# MyPO.net
KiCad netlist of a schematic drawn in EAGLE
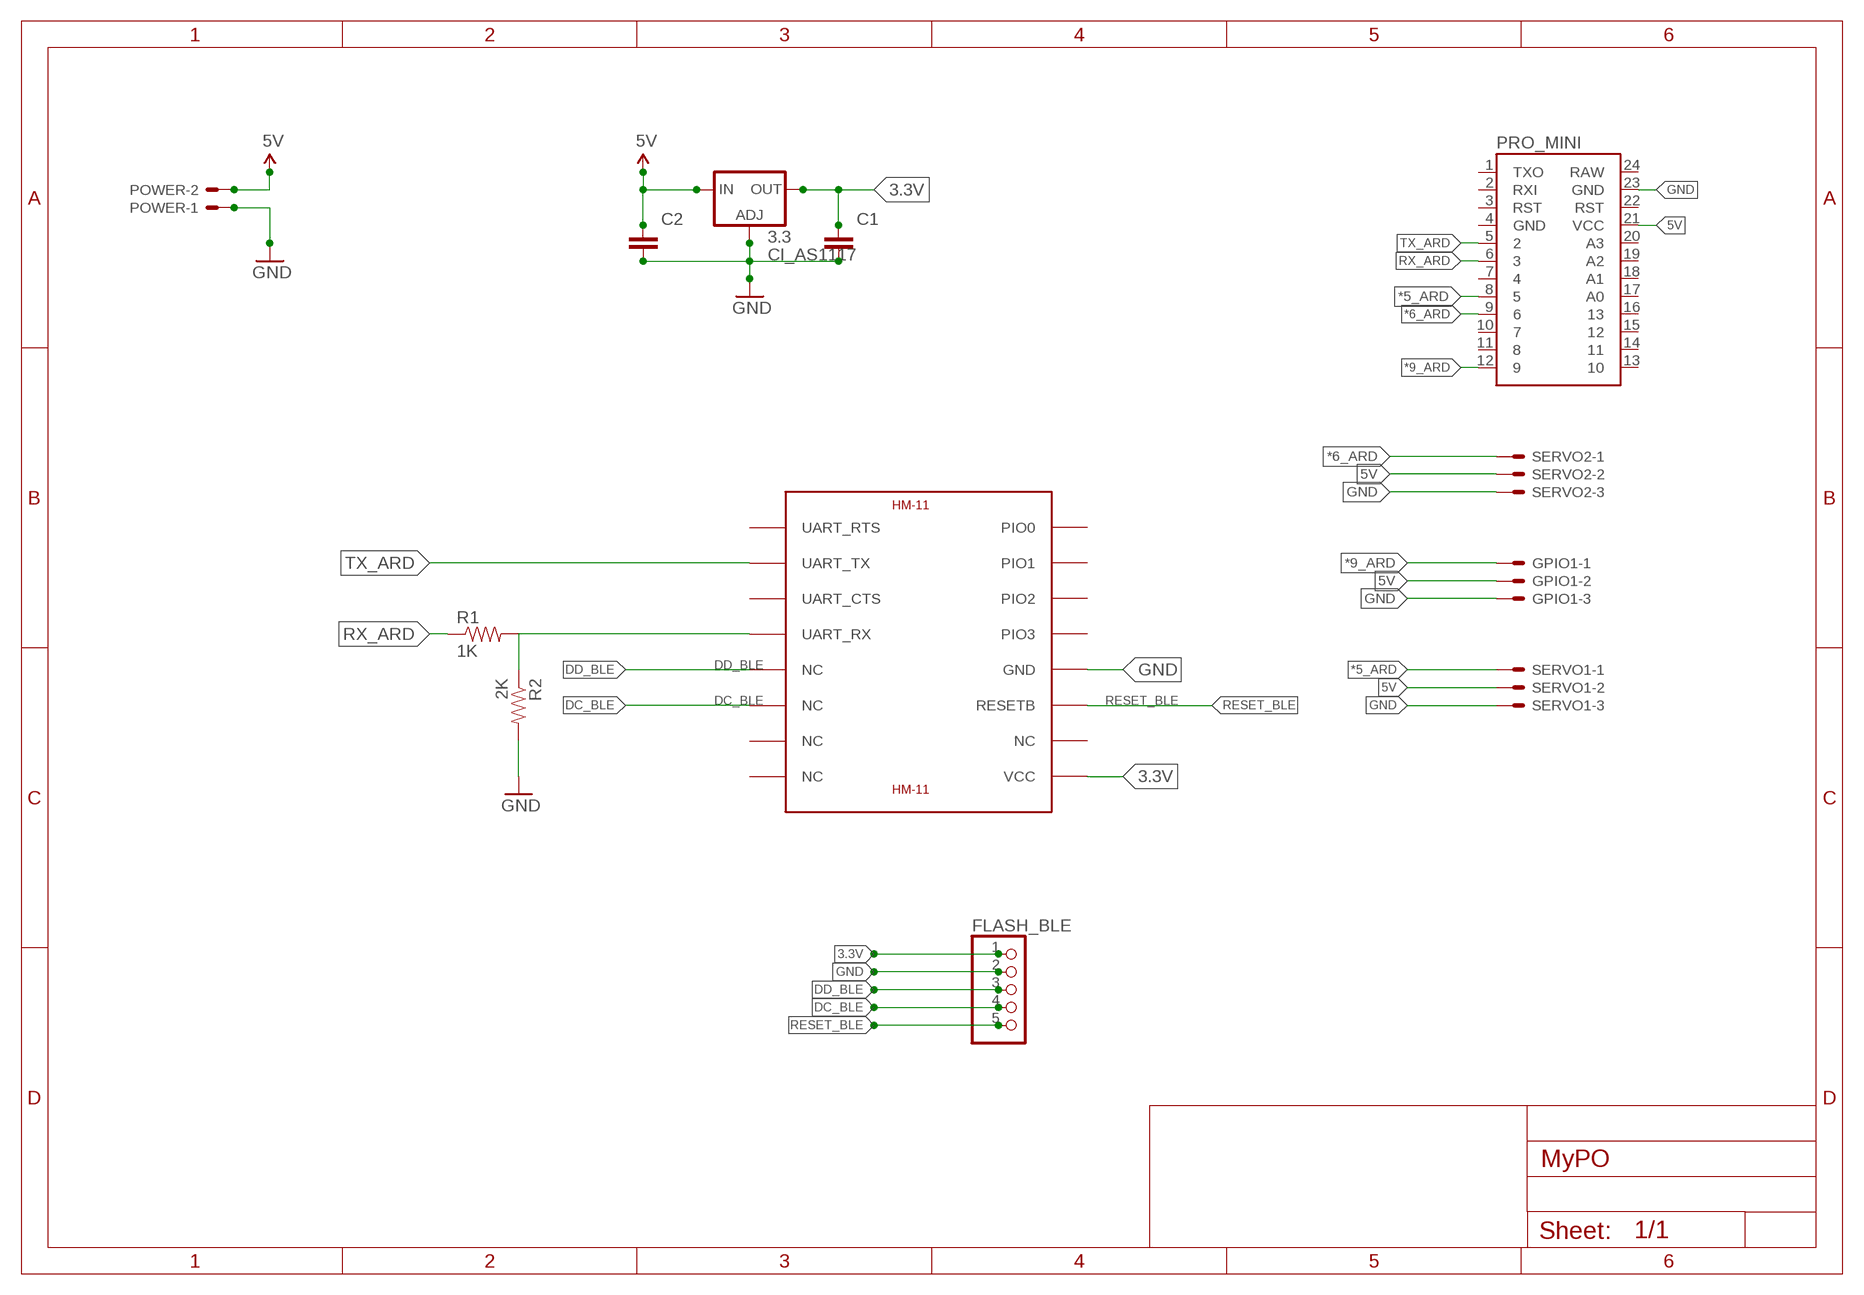
[diagram p0: schematic, sheet 1]

(export (version "E")
  (design (tool "Eeschema 10.0.6"))
  (components
    (comp (ref "3.3")
      (value "CI_AS1117")
      (footprint "eagle-import:DPACK")
      (libsource (lib "eagle-import") (part "LD117A?DT-TR"))
    )
    (comp (ref "BLE")
      (value "HM-11")
      (footprint "eagle-import:HM-11")
      (libsource (lib "eagle-import") (part "HM-11"))
    )
    (comp (ref "C1")
      (value "CAPACITOR-0805")
      (footprint "eagle-import:C0805")
      (libsource (lib "eagle-import") (part "CAPACITOR-0805"))
    )
    (comp (ref "C2")
      (value "CAPACITOR-0805")
      (footprint "eagle-import:C0805")
      (libsource (lib "eagle-import") (part "CAPACITOR-0805"))
    )
    (comp (ref "FLASH_BLE")
      (value "PINHD-1X55X2MM")
      (footprint "eagle-import:1_05X2MM")
      (libsource (lib "eagle-import") (part "PINHD-1X55X2MM"))
    )
    (comp (ref "GPIO1")
      (value "JST-XH-03-PIN-LONG-PAD")
      (footprint "eagle-import:JST-XH-03-PACKAGE-LONG-PAD")
      (libsource (lib "eagle-import") (part "JST-XH-03-PIN-LONG-PAD"))
    )
    (comp (ref "POWER")
      (value "JST-XH-02-PIN-LONG-PAD")
      (footprint "eagle-import:JST-XH-02-PACKAGE-LONG-PAD")
      (libsource (lib "eagle-import") (part "JST-XH-02-PIN-LONG-PAD"))
    )
    (comp (ref "PRO_MINI")
      (value "ARDUINO_MINI")
      (footprint "eagle-import:ARDUINO_MINI")
      (libsource (lib "eagle-import") (part "ARDUINO_MINI"))
    )
    (comp (ref "R1")
      (value "1K")
      (footprint "eagle-import:R0805")
      (libsource (lib "eagle-import") (part "RESISTOR-0805"))
    )
    (comp (ref "R2")
      (value "2K")
      (footprint "eagle-import:R0805")
      (libsource (lib "eagle-import") (part "RESISTOR-0805"))
    )
    (comp (ref "SERVO1")
      (value "JST-XH-03-PIN-LONG-PAD")
      (footprint "eagle-import:JST-XH-03-PACKAGE-LONG-PAD")
      (libsource (lib "eagle-import") (part "JST-XH-03-PIN-LONG-PAD"))
    )
    (comp (ref "SERVO2")
      (value "JST-XH-03-PIN-LONG-PAD")
      (footprint "eagle-import:JST-XH-03-PACKAGE-LONG-PAD")
      (libsource (lib "eagle-import") (part "JST-XH-03-PIN-LONG-PAD"))
    )
  )
  (nets
    (net (code "1") (name "*5_ARD") (class "Default")
      (node (ref "PRO_MINI") (pin "8") (pinfunction "5_8") (pintype "bidirectional"))
      (node (ref "SERVO1") (pin "1") (pinfunction "S_1") (pintype "passive"))
    )
    (net (code "2") (name "*6_ARD") (class "Default")
      (node (ref "PRO_MINI") (pin "9") (pinfunction "6_9") (pintype "bidirectional"))
      (node (ref "SERVO2") (pin "1") (pinfunction "S_1") (pintype "passive"))
    )
    (net (code "3") (name "*9_ARD") (class "Default")
      (node (ref "GPIO1") (pin "1") (pinfunction "S_1") (pintype "passive"))
      (node (ref "PRO_MINI") (pin "12") (pinfunction "9_12") (pintype "bidirectional"))
    )
    (net (code "4") (name "3.3V") (class "Default")
      (node (ref "3.3") (pin "4") (pinfunction "OUT_4") (pintype "passive"))
      (node (ref "BLE") (pin "VCC") (pinfunction "VCC_VCC") (pintype "bidirectional"))
      (node (ref "C1") (pin "1") (pinfunction "1_1") (pintype "passive"))
      (node (ref "FLASH_BLE") (pin "1") (pinfunction "1_1") (pintype "passive"))
    )
    (net (code "5") (name "5V") (class "Default")
      (node (ref "3.3") (pin "3") (pinfunction "IN_3") (pintype "input"))
      (node (ref "C2") (pin "1") (pinfunction "1_1") (pintype "passive"))
      (node (ref "GPIO1") (pin "2") (pinfunction "S_2") (pintype "passive"))
      (node (ref "POWER") (pin "2") (pinfunction "S_2") (pintype "passive"))
      (node (ref "PRO_MINI") (pin "21") (pinfunction "VCC_21") (pintype "bidirectional"))
      (node (ref "SERVO1") (pin "2") (pinfunction "S_2") (pintype "passive"))
      (node (ref "SERVO2") (pin "2") (pinfunction "S_2") (pintype "passive"))
    )
    (net (code "6") (name "DC_BLE") (class "Default")
      (node (ref "BLE") (pin "NC@6") (pinfunction "NC_NC@6") (pintype "bidirectional"))
      (node (ref "FLASH_BLE") (pin "4") (pinfunction "4_4") (pintype "passive"))
    )
    (net (code "7") (name "DD_BLE") (class "Default")
      (node (ref "BLE") (pin "NC@5") (pinfunction "NC_NC@5") (pintype "bidirectional"))
      (node (ref "FLASH_BLE") (pin "3") (pinfunction "3_3") (pintype "passive"))
    )
    (net (code "8") (name "GND") (class "Default")
      (node (ref "3.3") (pin "1") (pinfunction "ADJ_1") (pintype "input"))
      (node (ref "BLE") (pin "GND") (pinfunction "GND_GND") (pintype "bidirectional"))
      (node (ref "C1") (pin "2") (pinfunction "2_2") (pintype "passive"))
      (node (ref "C2") (pin "2") (pinfunction "2_2") (pintype "passive"))
      (node (ref "FLASH_BLE") (pin "2") (pinfunction "2_2") (pintype "passive"))
      (node (ref "GPIO1") (pin "3") (pinfunction "S_3") (pintype "passive"))
      (node (ref "POWER") (pin "1") (pinfunction "S_1") (pintype "passive"))
      (node (ref "PRO_MINI") (pin "23") (pinfunction "GND_23") (pintype "bidirectional"))
      (node (ref "R2") (pin "2") (pinfunction "2_2") (pintype "passive"))
      (node (ref "SERVO1") (pin "3") (pinfunction "S_3") (pintype "passive"))
      (node (ref "SERVO2") (pin "3") (pinfunction "S_3") (pintype "passive"))
    )
    (net (code "9") (name "Net-(BLE-PadUART_RX)") (class "Default")
      (node (ref "BLE") (pin "UART_RX") (pinfunction "UART_RX_UART_RX") (pintype "bidirectional"))
      (node (ref "R1") (pin "2") (pinfunction "2_2") (pintype "passive"))
      (node (ref "R2") (pin "1") (pinfunction "1_1") (pintype "passive"))
    )
    (net (code "10") (name "RESET_BLE") (class "Default")
      (node (ref "BLE") (pin "RESETB") (pinfunction "RESETB_RESETB") (pintype "bidirectional"))
      (node (ref "FLASH_BLE") (pin "5") (pinfunction "5_5") (pintype "passive"))
    )
    (net (code "11") (name "RX_ARD") (class "Default")
      (node (ref "PRO_MINI") (pin "6") (pinfunction "3_6") (pintype "bidirectional"))
      (node (ref "R1") (pin "1") (pinfunction "1_1") (pintype "passive"))
    )
    (net (code "12") (name "TX_ARD") (class "Default")
      (node (ref "BLE") (pin "UART_TX") (pinfunction "UART_TX_UART_TX") (pintype "bidirectional"))
      (node (ref "PRO_MINI") (pin "5") (pinfunction "2_5") (pintype "bidirectional"))
    )
    (net (code "13") (name "unconnected-(BLE-NC-PadNC@7)") (class "Default")
      (node (ref "BLE") (pin "NC@7") (pinfunction "NC_NC@7") (pintype "bidirectional"))
    )
    (net (code "14") (name "unconnected-(BLE-NC-PadNC@8)") (class "Default")
      (node (ref "BLE") (pin "NC@8") (pinfunction "NC_NC@8") (pintype "bidirectional"))
    )
    (net (code "15") (name "unconnected-(BLE-NC-PadNC@10)") (class "Default")
      (node (ref "BLE") (pin "NC@10") (pinfunction "NC_NC@10") (pintype "bidirectional"))
    )
    (net (code "16") (name "unconnected-(BLE-PadPIO0)") (class "Default")
      (node (ref "BLE") (pin "PIO0") (pinfunction "PIO0_PIO0") (pintype "bidirectional"))
    )
    (net (code "17") (name "unconnected-(BLE-PadPIO1)") (class "Default")
      (node (ref "BLE") (pin "PIO1") (pinfunction "PIO1_PIO1") (pintype "bidirectional"))
    )
    (net (code "18") (name "unconnected-(BLE-PadPIO2)") (class "Default")
      (node (ref "BLE") (pin "PIO2") (pinfunction "PIO2_PIO2") (pintype "bidirectional"))
    )
    (net (code "19") (name "unconnected-(BLE-PadPIO3)") (class "Default")
      (node (ref "BLE") (pin "PIO3") (pinfunction "PIO3_PIO3") (pintype "bidirectional"))
    )
    (net (code "20") (name "unconnected-(BLE-PadUART_CTS)") (class "Default")
      (node (ref "BLE") (pin "UART_CTS") (pinfunction "UART_CTS_UART_CTS") (pintype "bidirectional"))
    )
    (net (code "21") (name "unconnected-(BLE-PadUART_RTS)") (class "Default")
      (node (ref "BLE") (pin "UART_RTS") (pinfunction "UART_RTS_UART_RTS") (pintype "bidirectional"))
    )
    (net (code "22") (name "unconnected-(PRO_MINI-4-Pad7)") (class "Default")
      (node (ref "PRO_MINI") (pin "7") (pinfunction "4_7") (pintype "bidirectional"))
    )
    (net (code "23") (name "unconnected-(PRO_MINI-7-Pad10)") (class "Default")
      (node (ref "PRO_MINI") (pin "10") (pinfunction "7_10") (pintype "bidirectional"))
    )
    (net (code "24") (name "unconnected-(PRO_MINI-8-Pad11)") (class "Default")
      (node (ref "PRO_MINI") (pin "11") (pinfunction "8_11") (pintype "bidirectional"))
    )
    (net (code "25") (name "unconnected-(PRO_MINI-10-Pad13)") (class "Default")
      (node (ref "PRO_MINI") (pin "13") (pinfunction "10_13") (pintype "bidirectional"))
    )
    (net (code "26") (name "unconnected-(PRO_MINI-11-Pad14)") (class "Default")
      (node (ref "PRO_MINI") (pin "14") (pinfunction "11_14") (pintype "bidirectional"))
    )
    (net (code "27") (name "unconnected-(PRO_MINI-12-Pad15)") (class "Default")
      (node (ref "PRO_MINI") (pin "15") (pinfunction "12_15") (pintype "bidirectional"))
    )
    (net (code "28") (name "unconnected-(PRO_MINI-13-Pad16)") (class "Default")
      (node (ref "PRO_MINI") (pin "16") (pinfunction "13_16") (pintype "bidirectional"))
    )
    (net (code "29") (name "unconnected-(PRO_MINI-A0-Pad17)") (class "Default")
      (node (ref "PRO_MINI") (pin "17") (pinfunction "A0_17") (pintype "bidirectional"))
    )
    (net (code "30") (name "unconnected-(PRO_MINI-A1-Pad18)") (class "Default")
      (node (ref "PRO_MINI") (pin "18") (pinfunction "A1_18") (pintype "bidirectional"))
    )
    (net (code "31") (name "unconnected-(PRO_MINI-A2-Pad19)") (class "Default")
      (node (ref "PRO_MINI") (pin "19") (pinfunction "A2_19") (pintype "bidirectional"))
    )
    (net (code "32") (name "unconnected-(PRO_MINI-A3-Pad20)") (class "Default")
      (node (ref "PRO_MINI") (pin "20") (pinfunction "A3_20") (pintype "bidirectional"))
    )
    (net (code "33") (name "unconnected-(PRO_MINI-GND-Pad4)") (class "Default")
      (node (ref "PRO_MINI") (pin "4") (pinfunction "GND_4") (pintype "bidirectional"))
    )
    (net (code "34") (name "unconnected-(PRO_MINI-RAW-Pad24)") (class "Default")
      (node (ref "PRO_MINI") (pin "24") (pinfunction "RAW_24") (pintype "bidirectional"))
    )
    (net (code "35") (name "unconnected-(PRO_MINI-RST-Pad3)") (class "Default")
      (node (ref "PRO_MINI") (pin "3") (pinfunction "RST_3") (pintype "bidirectional"))
    )
    (net (code "36") (name "unconnected-(PRO_MINI-RST-Pad22)") (class "Default")
      (node (ref "PRO_MINI") (pin "22") (pinfunction "RST_22") (pintype "bidirectional"))
    )
    (net (code "37") (name "unconnected-(PRO_MINI-RXI-Pad2)") (class "Default")
      (node (ref "PRO_MINI") (pin "2") (pinfunction "RXI_2") (pintype "bidirectional"))
    )
    (net (code "38") (name "unconnected-(PRO_MINI-TXO-Pad1)") (class "Default")
      (node (ref "PRO_MINI") (pin "1") (pinfunction "TXO_1") (pintype "bidirectional"))
    )
  )
)
